# ACDC.net
KiCad netlist of a schematic drawn in EasyEDA Pro
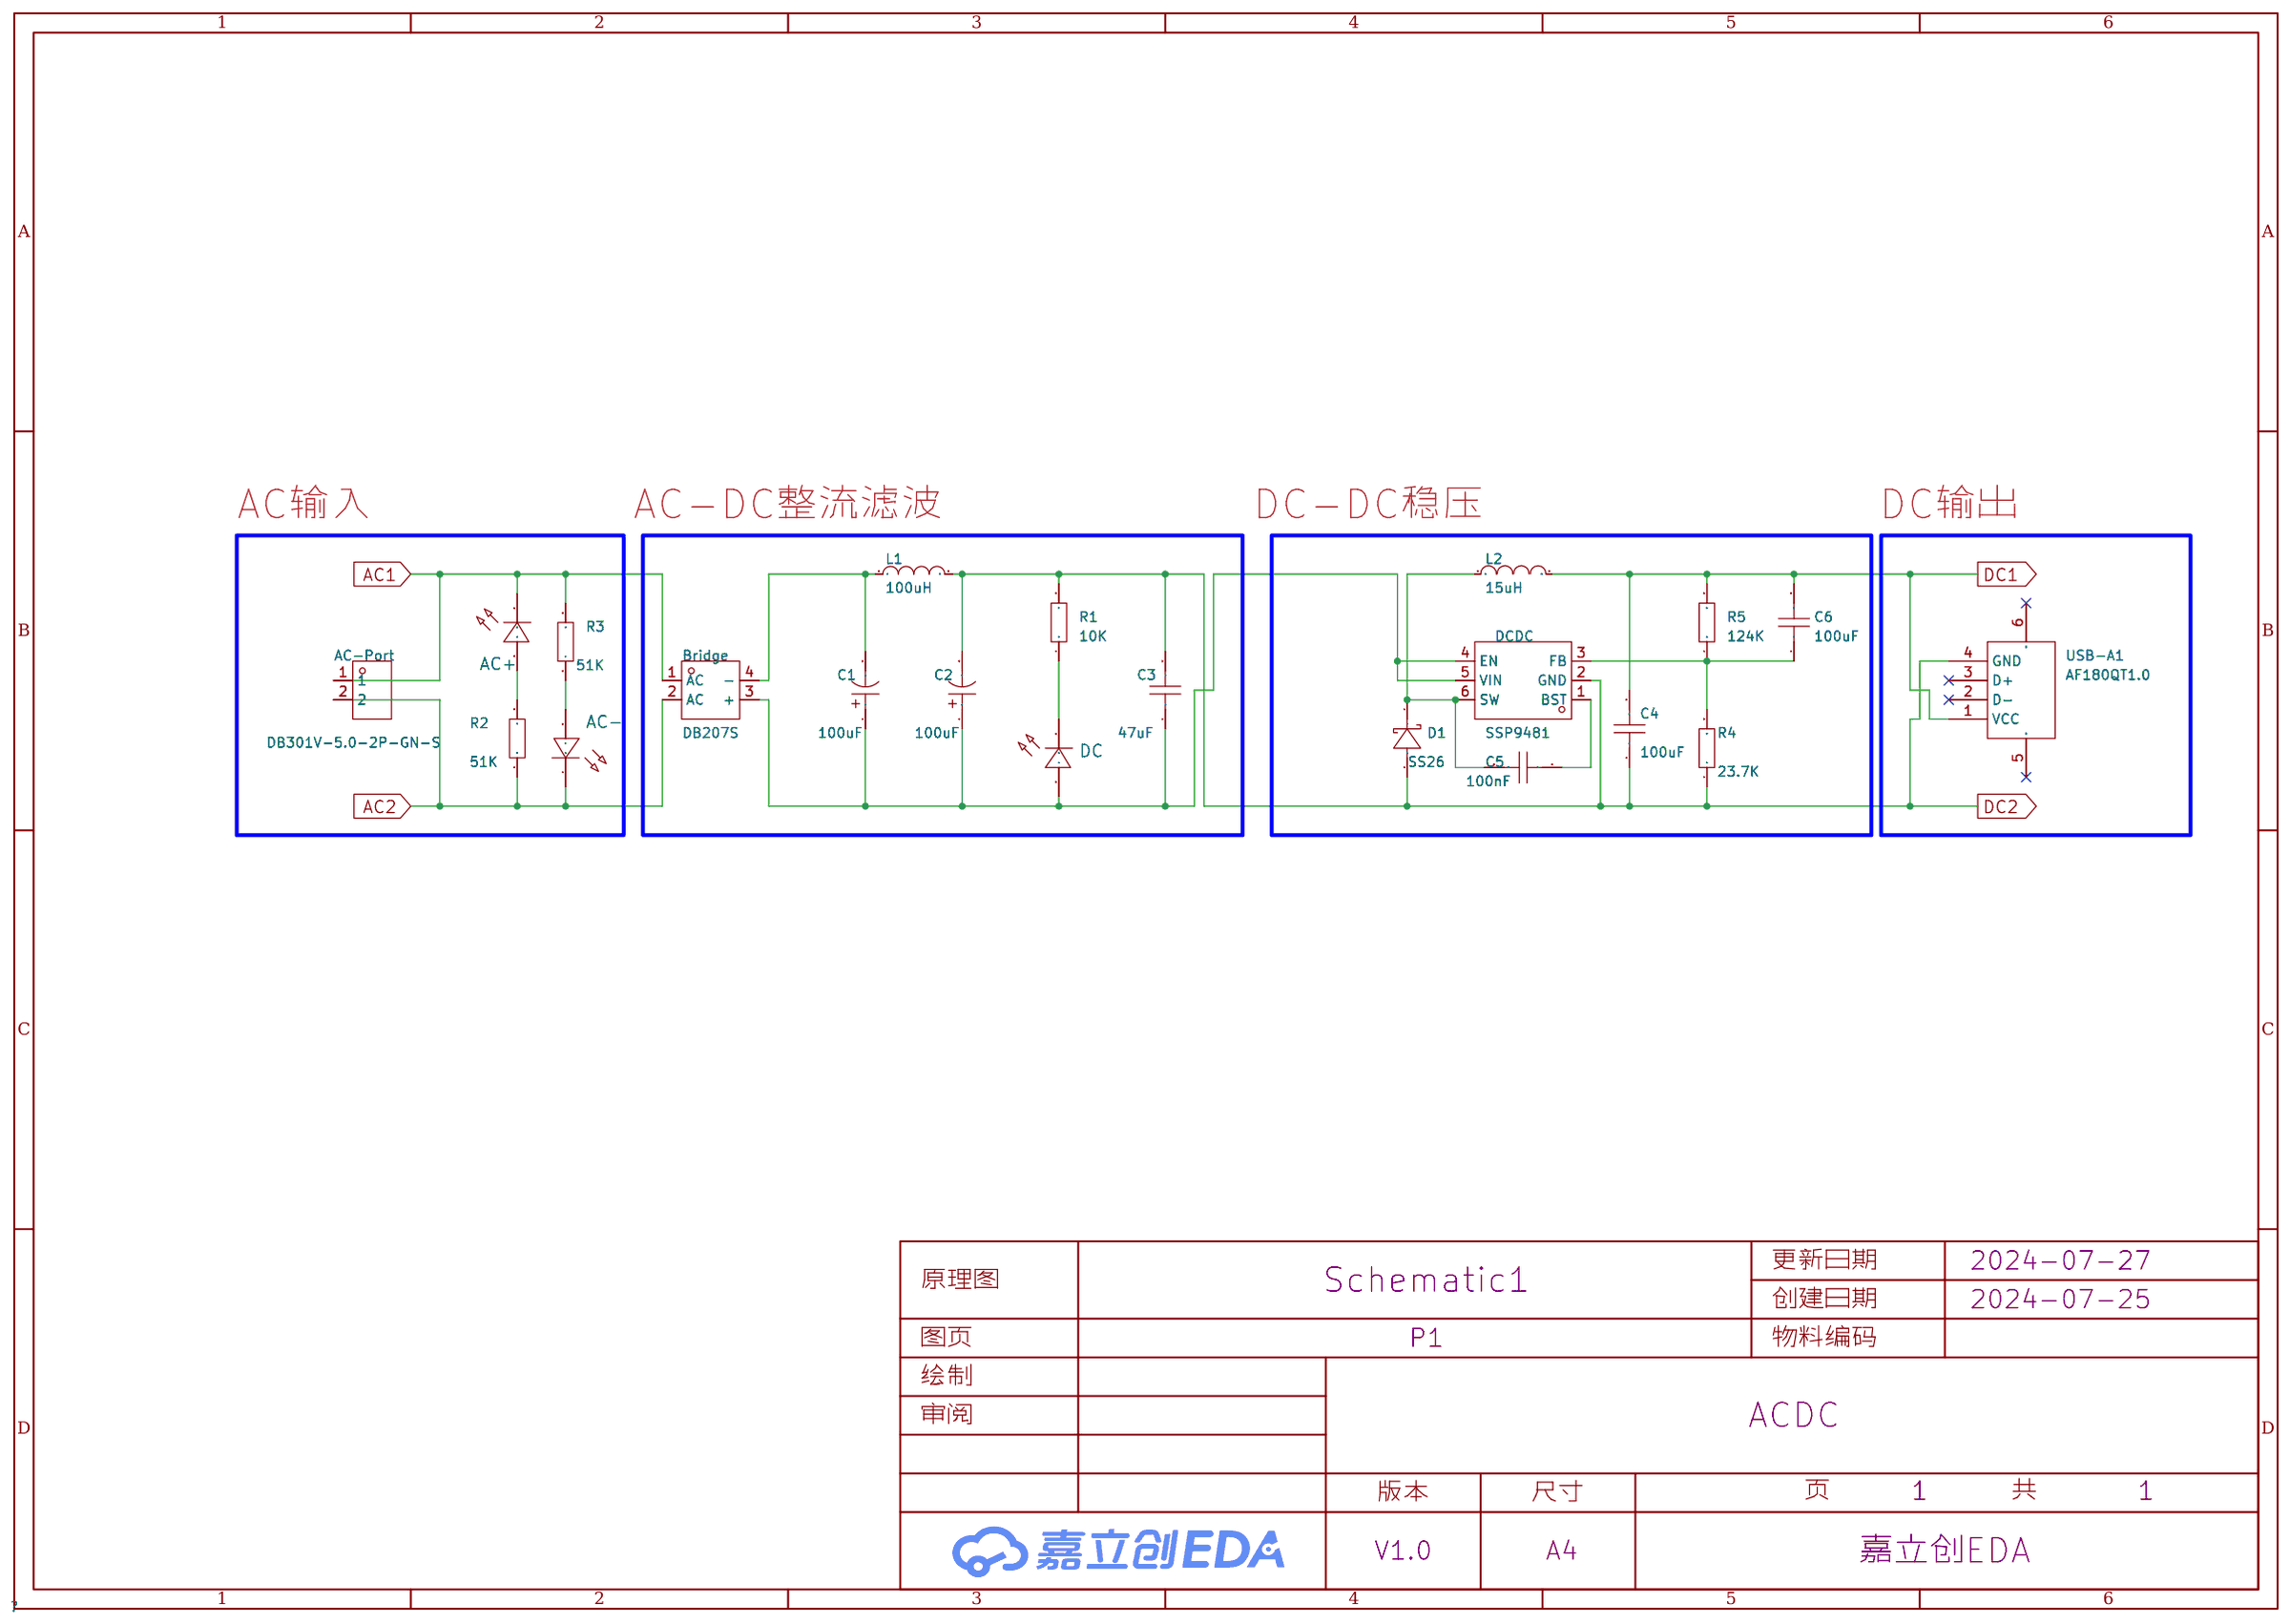
[diagram p0: schematic sheet]

(export (version "E")
  (design (tool "Eeschema 10.0.6"))
  (components
    (comp (ref "AC+")
      (value "~")
      (footprint "easyedapro:LED_0603")
      (libsource (lib "easyedapro") (part "LED_R"))
    )
    (comp (ref "AC-")
      (value "~")
      (footprint "easyedapro:LED_0603")
      (libsource (lib "easyedapro") (part "LED_R"))
    )
    (comp (ref "AC-Port")
      (value "DB301V-5.0-2P-GN-S")
      (footprint "easyedapro:CONN-TH_2P-P5.00_DB301V-5.0-2P-GN-S")
      (fields (field (name "Manufacturer") "DORABO(地博电气)"))
      (libsource (lib "easyedapro") (part "DB301V-5.0-2P-GN-S"))
    )
    (comp (ref "Bridge")
      (value "DB207S")
      (footprint "easyedapro:DBS_L8.4-W6.4-P5.10-LS10.2-TL")
      (description "正向压降(Vf):1.1V@1A;直流反向耐压(Vr):1kV;整流电流:2A;正向浪涌电流(Ifsm):50A;")
      (fields (field (name "Manufacturer") "MDD(辰达半导体)"))
      (libsource (lib "easyedapro") (part "DB207S_C29174"))
    )
    (comp (ref "C1")
      (value "100uF")
      (footprint "easyedapro:CAP-TH_BD6.3-P2.50-D0.6-FD-1")
      (description "容值:33uF;精度:±20%;额定电压:63V;")
      (fields
        (field (name "Manufacturer Part") "SPT1JM330E08ORVZC")
        (field (name "Manufacturer") "Yunxing(云星)")
      )
      (libsource (lib "easyedapro") (part "SPT1JM330E08ORVZC"))
    )
    (comp (ref "C2")
      (value "100uF")
      (footprint "easyedapro:CAP-TH_BD6.3-P2.50-D0.6-FD-1")
      (description "容值:33uF;精度:±20%;额定电压:63V;")
      (fields
        (field (name "Manufacturer Part") "SPT1JM330E08ORVZC")
        (field (name "Manufacturer") "Yunxing(云星)")
      )
      (libsource (lib "easyedapro") (part "SPT1JM330E08ORVZC"))
    )
    (comp (ref "C3")
      (value "47uF")
      (footprint "easyedapro:C0603")
      (libsource (lib "easyedapro") (part "CapAcitance"))
    )
    (comp (ref "C4")
      (value "100uF")
      (footprint "easyedapro:C0603")
      (libsource (lib "easyedapro") (part "CapAcitance"))
    )
    (comp (ref "C5")
      (value "100nF")
      (footprint "easyedapro:C0603")
      (libsource (lib "easyedapro") (part "CapAcitance"))
    )
    (comp (ref "C6")
      (value "100uF")
      (footprint "easyedapro:C0603")
      (libsource (lib "easyedapro") (part "CapAcitance"))
    )
    (comp (ref "D1")
      (value "SS26")
      (footprint "easyedapro:SMA_L4.2-W2.6-LS5.3-RD")
      (description "二极管配置:独立式;正向压降(Vf):700mV@2A;直流反向耐压(Vr):60V;平均整流电流(Io):2A;")
      (fields (field (name "Manufacturer") "CJ(江苏长电/长晶)"))
      (libsource (lib "easyedapro") (part "SS26_C2923952"))
    )
    (comp (ref "DC")
      (value "~")
      (footprint "easyedapro:LED_0603")
      (libsource (lib "easyedapro") (part "LED_R"))
    )
    (comp (ref "DCDC")
      (value "SSP9481")
      (footprint "easyedapro:SOT-23-6_L2.9-W1.6-P0.95-LS2.8-BR")
      (description "输入电压:4.5V~80V;输出电流(最大值):1A;")
      (fields (field (name "Manufacturer") "Siproin(上海矽朋)"))
      (libsource (lib "easyedapro") (part "SSP9481"))
    )
    (comp (ref "L1")
      (value "100uH")
      (footprint "easyedapro:IND-SMD_L11.6-W10.1")
      (description "电感值:33uH;精度:±20%;额定电流:3.2A;饱和电流(Isat):5A;直流电阻(DCR):110mΩ;")
      (fields (field (name "Manufacturer Part") "BCIHP1040SC-330M") (field (name "Manufacturer") "BC(台湾诚阳)"))
      (libsource (lib "easyedapro") (part "BCIHP1040SC-330M"))
    )
    (comp (ref "L2")
      (value "15uH")
      (footprint "easyedapro:L0603")
      (libsource (lib "easyedapro") (part "SDFL1608S100KTF"))
    )
    (comp (ref "R1") (value "10K") (footprint "easyedapro:R0603") (libsource (lib "easyedapro") (part "电阻")))
    (comp (ref "R2") (value "51K") (footprint "easyedapro:R0603") (libsource (lib "easyedapro") (part "电阻")))
    (comp (ref "R3") (value "51K") (footprint "easyedapro:R0603") (libsource (lib "easyedapro") (part "电阻")))
    (comp (ref "R4")
      (value "23.7K")
      (footprint "easyedapro:R0603")
      (libsource (lib "easyedapro") (part "电阻"))
    )
    (comp (ref "R5") (value "124K") (footprint "easyedapro:R0603") (libsource (lib "easyedapro") (part "电阻")))
    (comp (ref "USB-A1")
      (value "AF180QT1.0")
      (footprint "easyedapro:USB-A-SMD_AF180QT1.0")
      (description "连接器类型:Type-A;标准:USB 2.0;公母:母;端口数量:1;触点数量:4P;安装方式:卧贴;额定电流 - 电源:-;工作温度范围:-;")
      (fields (field (name "Manufacturer") "SHOU HAN(首韩)"))
      (libsource (lib "easyedapro") (part "AF180QT1.0"))
    )
  )
  (nets
    (net (code "1") (name "AC1") (class "Default")
      (node (ref "AC+") (pin "1") (pinfunction "C_1") (pintype "input"))
      (node (ref "AC-Port") (pin "1") (pinfunction "1_1") (pintype "unspecified"))
      (node (ref "Bridge") (pin "1") (pinfunction "AC_1") (pintype "unspecified"))
      (node (ref "R3") (pin "2") (pinfunction "2_2") (pintype "input"))
    )
    (net (code "2") (name "AC2") (class "Default")
      (node (ref "AC-") (pin "1") (pinfunction "C_1") (pintype "input"))
      (node (ref "AC-Port") (pin "2") (pinfunction "2_2") (pintype "unspecified"))
      (node (ref "Bridge") (pin "2") (pinfunction "AC_2") (pintype "unspecified"))
      (node (ref "R2") (pin "1") (pinfunction "1_1") (pintype "input"))
    )
    (net (code "3") (name "DC1") (class "Default")
      (node (ref "C4") (pin "2") (pinfunction "2_2") (pintype "input"))
      (node (ref "C6") (pin "2") (pinfunction "2_2") (pintype "input"))
      (node (ref "L2") (pin "2") (pinfunction "2_2") (pintype "unspecified"))
      (node (ref "R5") (pin "2") (pinfunction "2_2") (pintype "input"))
      (node (ref "USB-A1") (pin "1") (pinfunction "VCC_1") (pintype "input"))
    )
    (net (code "4") (name "DC2") (class "Default")
      (node (ref "C2") (pin "2") (pinfunction "2_2") (pintype "input"))
      (node (ref "C3") (pin "2") (pinfunction "2_2") (pintype "input"))
      (node (ref "C4") (pin "1") (pinfunction "1_1") (pintype "input"))
      (node (ref "D1") (pin "2") (pinfunction "A_2") (pintype "unspecified"))
      (node (ref "DCDC") (pin "2") (pinfunction "GND_2") (pintype "unspecified"))
      (node (ref "L1") (pin "2") (pinfunction "2_2") (pintype "unspecified"))
      (node (ref "R1") (pin "2") (pinfunction "2_2") (pintype "input"))
      (node (ref "R4") (pin "1") (pinfunction "1_1") (pintype "input"))
      (node (ref "USB-A1") (pin "4") (pinfunction "GND_4") (pintype "input"))
    )
    (net (code "5") (name "Net-(AC+-A)") (class "Default")
      (node (ref "AC+") (pin "2") (pinfunction "A_2") (pintype "input"))
      (node (ref "R2") (pin "2") (pinfunction "2_2") (pintype "input"))
    )
    (net (code "6") (name "Net-(AC--A)") (class "Default")
      (node (ref "AC-") (pin "2") (pinfunction "A_2") (pintype "input"))
      (node (ref "R3") (pin "1") (pinfunction "1_1") (pintype "input"))
    )
    (net (code "7") (name "Net-(Bridge-+)") (class "Default")
      (node (ref "Bridge") (pin "3") (pinfunction "+_3") (pintype "unspecified"))
      (node (ref "C1") (pin "1") (pinfunction "1_1") (pintype "input"))
      (node (ref "C2") (pin "1") (pinfunction "1_1") (pintype "input"))
      (node (ref "C3") (pin "1") (pinfunction "1_1") (pintype "input"))
      (node (ref "DC") (pin "2") (pinfunction "A_2") (pintype "input"))
      (node (ref "DCDC") (pin "4") (pinfunction "EN_4") (pintype "unspecified"))
      (node (ref "DCDC") (pin "5") (pinfunction "VIN_5") (pintype "unspecified"))
    )
    (net (code "8") (name "Net-(Bridge--)") (class "Default")
      (node (ref "Bridge") (pin "4") (pinfunction "-_4") (pintype "unspecified"))
      (node (ref "C1") (pin "2") (pinfunction "2_2") (pintype "input"))
      (node (ref "L1") (pin "1") (pinfunction "1_1") (pintype "unspecified"))
    )
    (net (code "9") (name "Net-(D1-K)") (class "Default")
      (node (ref "C5") (pin "2") (pinfunction "2_2") (pintype "input"))
      (node (ref "D1") (pin "1") (pinfunction "K_1") (pintype "unspecified"))
      (node (ref "DCDC") (pin "6") (pinfunction "SW_6") (pintype "unspecified"))
      (node (ref "L2") (pin "1") (pinfunction "1_1") (pintype "unspecified"))
    )
    (net (code "10") (name "Net-(DC-C)") (class "Default")
      (node (ref "DC") (pin "1") (pinfunction "C_1") (pintype "input"))
      (node (ref "R1") (pin "1") (pinfunction "1_1") (pintype "input"))
    )
    (net (code "11") (name "Net-(DCDC-BST)") (class "Default")
      (node (ref "C5") (pin "1") (pinfunction "1_1") (pintype "input"))
      (node (ref "DCDC") (pin "1") (pinfunction "BST_1") (pintype "unspecified"))
    )
    (net (code "12") (name "Net-(DCDC-FB)") (class "Default")
      (node (ref "C6") (pin "1") (pinfunction "1_1") (pintype "input"))
      (node (ref "DCDC") (pin "3") (pinfunction "FB_3") (pintype "unspecified"))
      (node (ref "R4") (pin "2") (pinfunction "2_2") (pintype "input"))
      (node (ref "R5") (pin "1") (pinfunction "1_1") (pintype "input"))
    )
    (net (code "13") (name "unconnected-(USB-A1-D+-Pad3)") (class "Default")
      (node (ref "USB-A1") (pin "3") (pinfunction "D+_3") (pintype "input+no_connect"))
    )
    (net (code "14") (name "unconnected-(USB-A1-D--Pad2)") (class "Default")
      (node (ref "USB-A1") (pin "2") (pinfunction "D-_2") (pintype "input+no_connect"))
    )
    (net (code "15") (name "unconnected-(USB-A1-SH1-Pad5)") (class "Default")
      (node (ref "USB-A1") (pin "5") (pinfunction "SH1_5") (pintype "unspecified+no_connect"))
    )
    (net (code "16") (name "unconnected-(USB-A1-SH2-Pad6)") (class "Default")
      (node (ref "USB-A1") (pin "6") (pinfunction "SH2_6") (pintype "unspecified+no_connect"))
    )
  )
)
